# Hard_Soft_JTAG_Socket.net
KiCad netlist of a schematic drawn in Altium Designer
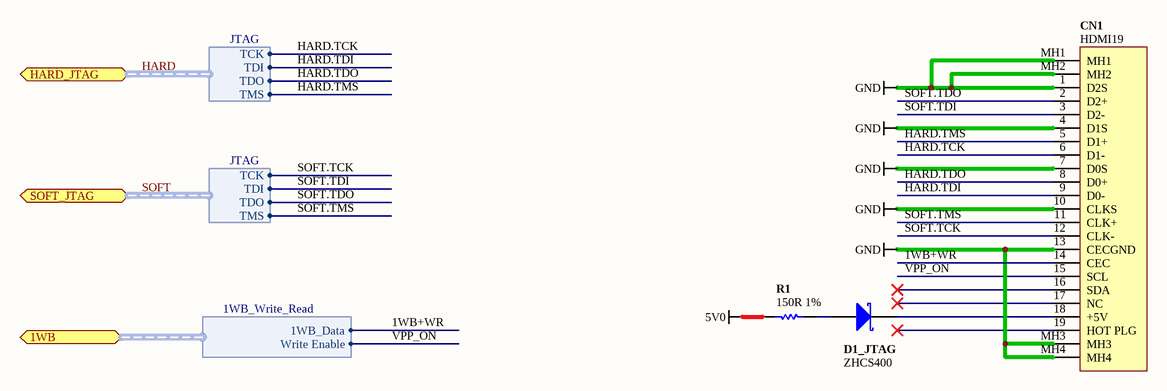
[diagram p0: Hard_Soft_JTAG_Socket.SchDoc]

(export (version "E")
  (design (tool "Eeschema 10.0.6"))
  (components
    (comp (ref "CN1")
      (value "HDMI19")
      (footprint "G3168-0500XXXX-00")
      (description "HDMI Socket; 19 Pin")
      (libsource (lib "AltiumDesignLibrary") (part "HDMI19"))
    )
    (comp (ref "D1_JTAG")
      (value "ZHCS400")
      (footprint "SOD323")
      (description "Schottky Diode, 400mA")
      (libsource (lib "AltiumDesignLibrary") (part "DIO-SCHOTTKY-1S"))
    )
    (comp (ref "R1")
      (value "150R 1%")
      (footprint "RESC1005-STAR")
      (description "Resistor, 150R 1% 0402 (1005)")
      (fields (field (name "TOLERANCE") "1 %"))
      (libsource (lib "AltiumDesignLibrary") (part "RES"))
    )
  )
  (nets
    (net (code "4") (name "/1WB+WR") (class "Default")
      (node (ref "CN1") (pin "14") (pinfunction "CEC_14") (pintype "passive"))
    )
    (net (code "5") (name "/HARD.TCK") (class "Default")
      (node (ref "CN1") (pin "6") (pinfunction "D1-_6") (pintype "passive"))
    )
    (net (code "6") (name "/HARD.TDI") (class "Default")
      (node (ref "CN1") (pin "9") (pinfunction "D0-_9") (pintype "passive"))
    )
    (net (code "7") (name "/HARD.TDO") (class "Default")
      (node (ref "CN1") (pin "8") (pinfunction "D0+_8") (pintype "passive"))
    )
    (net (code "8") (name "/HARD.TMS") (class "Default")
      (node (ref "CN1") (pin "5") (pinfunction "D1+_5") (pintype "passive"))
    )
    (net (code "10") (name "/SOFT.TCK") (class "Default")
      (node (ref "CN1") (pin "12") (pinfunction "CLK-_12") (pintype "passive"))
    )
    (net (code "11") (name "/SOFT.TDI") (class "Default")
      (node (ref "CN1") (pin "3") (pinfunction "D2-_3") (pintype "passive"))
    )
    (net (code "12") (name "/SOFT.TDO") (class "Default")
      (node (ref "CN1") (pin "2") (pinfunction "D2+_2") (pintype "passive"))
    )
    (net (code "13") (name "/SOFT.TMS") (class "Default")
      (node (ref "CN1") (pin "11") (pinfunction "CLK+_11") (pintype "passive"))
    )
    (net (code "15") (name "/VPP_ON") (class "Default")
      (node (ref "CN1") (pin "15") (pinfunction "SCL_15") (pintype "passive"))
    )
    (net (code "17") (name "5V0") (class "Default")
      (node (ref "R1") (pin "1") (pinfunction "1_1") (pintype "passive"))
    )
    (net (code "18") (name "GND") (class "Default")
      (node (ref "CN1") (pin "1") (pinfunction "D2S_1") (pintype "passive"))
      (node (ref "CN1") (pin "10") (pinfunction "CLKS_10") (pintype "passive"))
      (node (ref "CN1") (pin "13") (pinfunction "CECGND_13") (pintype "passive"))
      (node (ref "CN1") (pin "4") (pinfunction "D1S_4") (pintype "passive"))
      (node (ref "CN1") (pin "7") (pinfunction "D0S_7") (pintype "passive"))
      (node (ref "CN1") (pin "MH1") (pinfunction "MH1_MH1") (pintype "passive"))
      (node (ref "CN1") (pin "MH2") (pinfunction "MH2_MH2") (pintype "passive"))
      (node (ref "CN1") (pin "MH3") (pinfunction "MH3_MH3") (pintype "passive"))
      (node (ref "CN1") (pin "MH4") (pinfunction "MH4_MH4") (pintype "passive"))
    )
    (net (code "19") (name "Net-(CN1-+5V)") (class "Default")
      (node (ref "CN1") (pin "18") (pinfunction "+5V_18") (pintype "passive"))
      (node (ref "D1_JTAG") (pin "2") (pinfunction "K_2") (pintype "passive"))
    )
    (net (code "20") (name "Net-(D1_JTAG-A)") (class "Default")
      (node (ref "D1_JTAG") (pin "1") (pinfunction "A_1") (pintype "passive"))
      (node (ref "R1") (pin "2") (pinfunction "2_2") (pintype "passive"))
    )
    (net (code "21") (name "unconnected-(CN1-HOT_PLG-Pad19)") (class "Default")
      (node (ref "CN1") (pin "19") (pinfunction "HOT_PLG_19") (pintype "passive+no_connect"))
    )
    (net (code "22") (name "unconnected-(CN1-NC-Pad17)") (class "Default")
      (node (ref "CN1") (pin "17") (pinfunction "NC_17") (pintype "passive+no_connect"))
    )
    (net (code "23") (name "unconnected-(CN1-SDA-Pad16)") (class "Default")
      (node (ref "CN1") (pin "16") (pinfunction "SDA_16") (pintype "passive+no_connect"))
    )
  )
)
